# logi-edu.net
KiCad netlist of a schematic drawn in Altium Designer
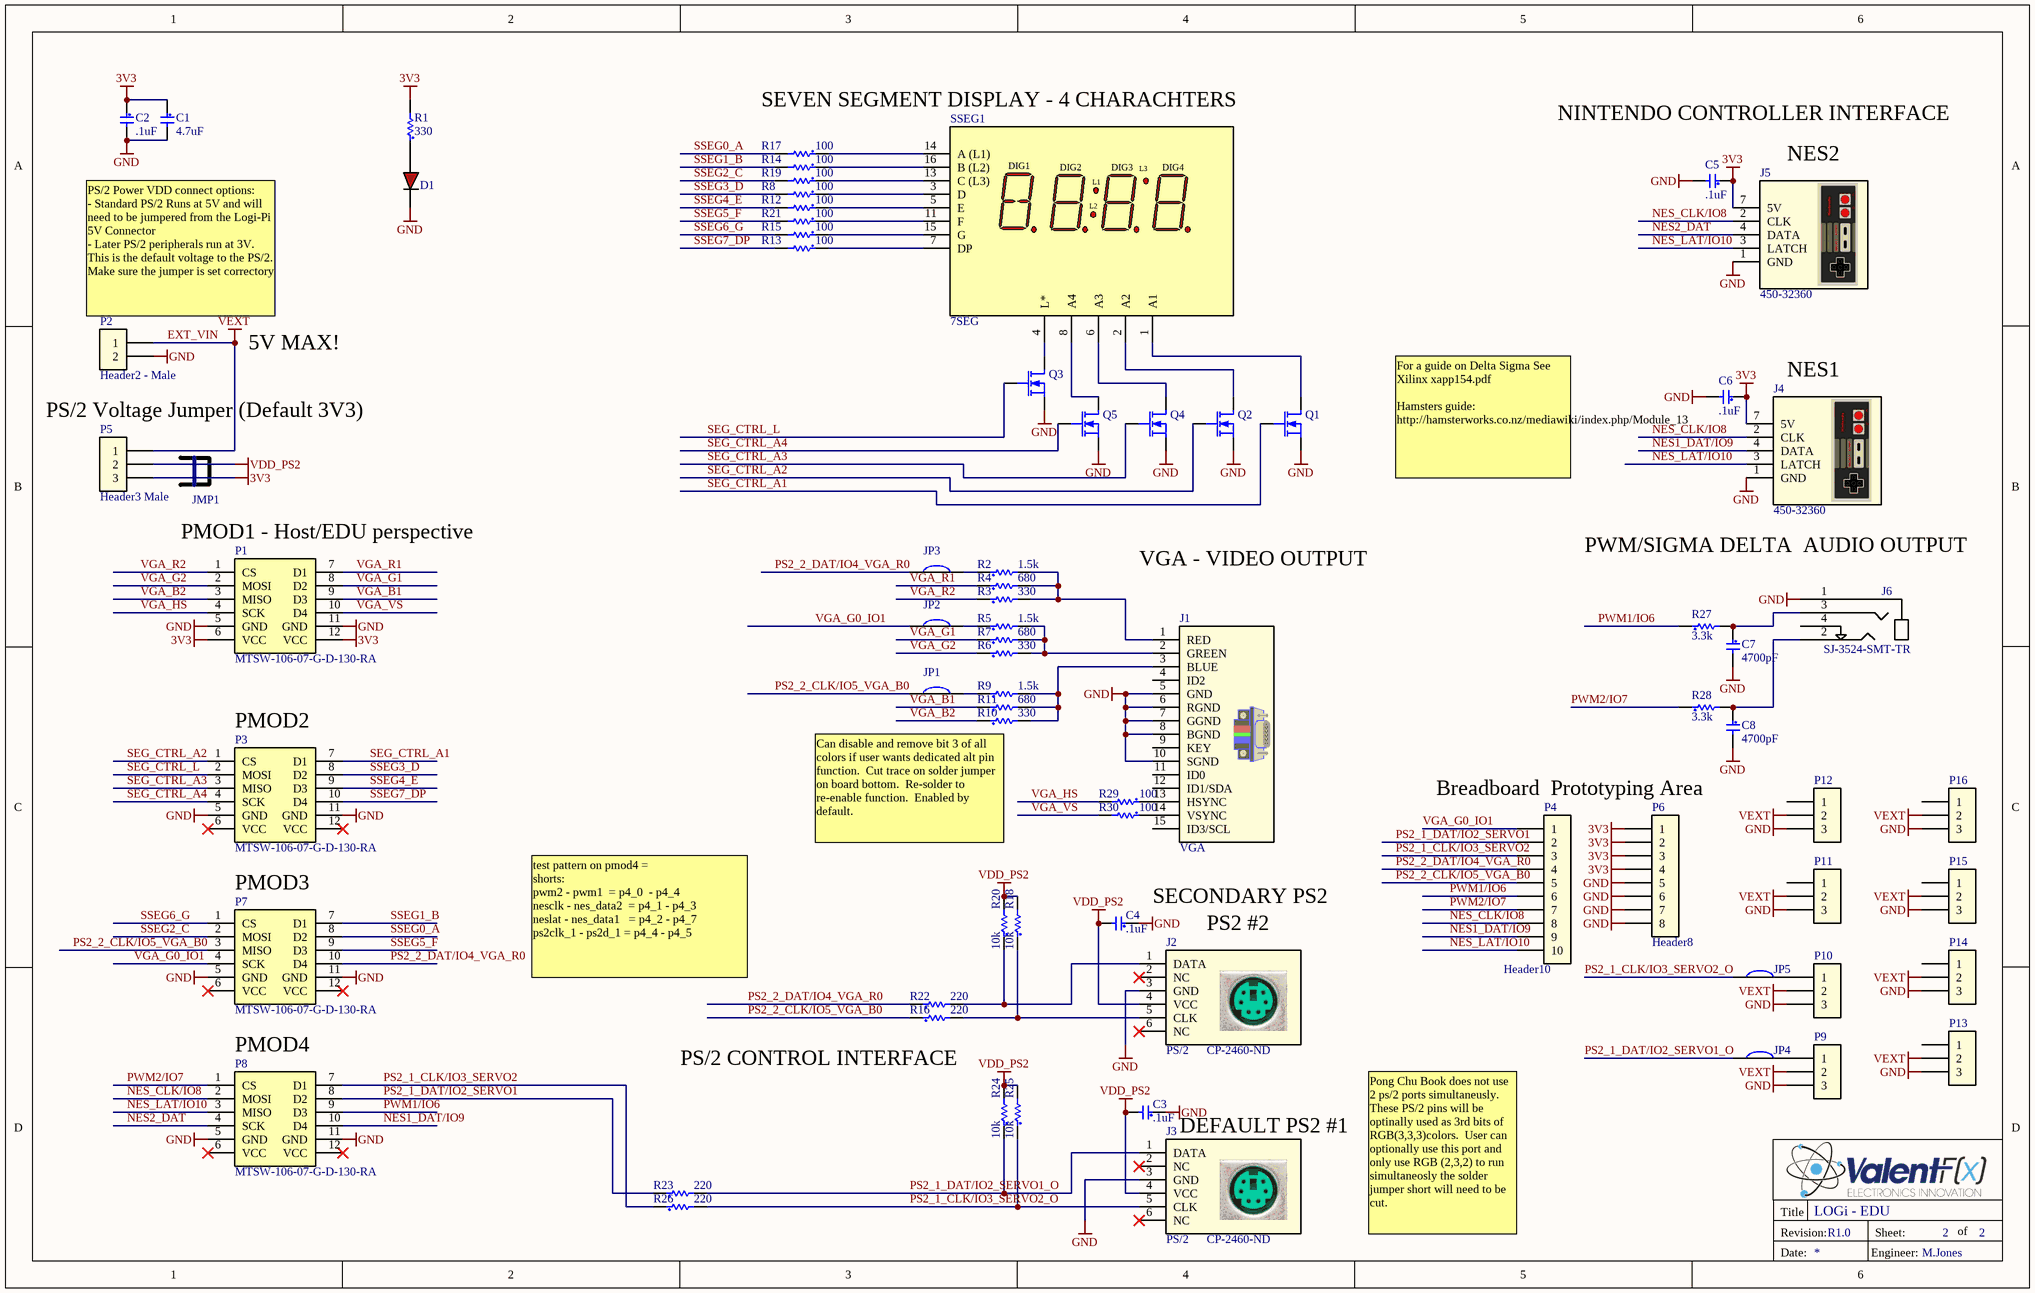
[diagram p0: logi-edu.SchDoc]

(export (version "E")
  (design (tool "Eeschema 10.0.6"))
  (components
    (comp (ref "C1")
      (value "4.7uF")
      (footprint "mRCL:C0603")
      (description "4.7uF 10volts Y5V +80-20% (MLCC) - SMD/SMT 0603")
      (fields
        (field (name "MANUFACTURER") "Murata")
        (field (name "MANUFACTURER PART NUMBER") "GRM188F51A475ZE20D")
      )
      (libsource (lib "mCapacitors") (part "C0603 - GRM188F51A475ZE20D"))
    )
    (comp (ref "C2")
      (value ".1uF")
      (footprint "mRCL:C0603")
      (description "0.1uF 50volts X7R 10% MLCC SMD/SMT 0603")
      (fields
        (field (name "MANUFACTURER") "Murata")
        (field (name "MANUFACTURER PART NUMBER") "GRM188R71H104KA93D")
      )
      (libsource (lib "mCapacitors") (part "C0603 - GRM188R71H104KA93D"))
    )
    (comp (ref "C3")
      (value ".1uF")
      (footprint "mRCL:C0603")
      (description "0.1uF 50volts X7R 10% MLCC SMD/SMT 0603")
      (fields
        (field (name "MANUFACTURER") "Murata")
        (field (name "MANUFACTURER PART NUMBER") "GRM188R71H104KA93D")
      )
      (libsource (lib "mCapacitors") (part "C0603 - GRM188R71H104KA93D"))
    )
    (comp (ref "C4")
      (value ".1uF")
      (footprint "mRCL:C0603")
      (description "0.1uF 50volts X7R 10% MLCC SMD/SMT 0603")
      (fields
        (field (name "MANUFACTURER") "Murata")
        (field (name "MANUFACTURER PART NUMBER") "GRM188R71H104KA93D")
      )
      (libsource (lib "mCapacitors") (part "C0603 - GRM188R71H104KA93D"))
    )
    (comp (ref "C5")
      (value ".1uF")
      (footprint "mRCL:C0603")
      (description "0.1uF 50volts X7R 10% MLCC SMD/SMT 0603")
      (fields
        (field (name "MANUFACTURER") "Murata")
        (field (name "MANUFACTURER PART NUMBER") "GRM188R71H104KA93D")
      )
      (libsource (lib "mCapacitors") (part "C0603 - GRM188R71H104KA93D"))
    )
    (comp (ref "C6")
      (value ".1uF")
      (footprint "mRCL:C0603")
      (description "0.1uF 50volts X7R 10% MLCC SMD/SMT 0603")
      (fields
        (field (name "MANUFACTURER") "Murata")
        (field (name "MANUFACTURER PART NUMBER") "GRM188R71H104KA93D")
      )
      (libsource (lib "mCapacitors") (part "C0603 - GRM188R71H104KA93D"))
    )
    (comp (ref "C7")
      (value "4700pF")
      (footprint "mrcl:C1206")
      (description "CAP CER 4700PF 50V 10% X7R 1206")
      (fields
        (field (name "MANUFACTURER") "Kemet")
        (field (name "MANUFACTURER PART NUMBER") "C1206C472K5RACTU")
      )
      (libsource (lib "mCapacitors") (part "C1206 - C1206C472K5RACTU"))
    )
    (comp (ref "C8")
      (value "4700pF")
      (footprint "mrcl:C1206")
      (description "CAP CER 4700PF 50V 10% X7R 1206")
      (fields
        (field (name "MANUFACTURER") "Kemet")
        (field (name "MANUFACTURER PART NUMBER") "C1206C472K5RACTU")
      )
      (libsource (lib "mCapacitors") (part "C1206 - C1206C472K5RACTU"))
    )
    (comp (ref "D1")
      (value "598-8010-107F")
      (footprint "LED_0603 - RED")
      (description "LED ALINGAP RED CLEAR 0603 SMD")
      (fields (field (name "MANUFACTURER") "Dialight"))
      (libsource (lib "mDiode") (part "LED0603 - 598-8010-107F"))
    )
    (comp (ref "J1")
      (value "VGA")
      (footprint "econnector:1-1734530-1")
      (description "CONN HD D-SUB RCPT R/A 15POS")
      (fields
        (field (name "MANUFACTURER") "TE Connectivity")
        (field (name "MANUFACTURER PART NUMBER") "1-1734530-1")
      )
      (libsource (lib "eConnector") (part "VGA - 1-1734530-1"))
    )
    (comp (ref "J2")
      (value "PS/2")
      (footprint "mconnector:MD-60S - PS/2")
      (description "CONN MINIDIN RECPT UNSHIELD 6POS - PS/2 mouse - keybaord")
      (fields
        (field (name "MANUFACTURER") "CUI Inc")
        (field (name "MANUFACTURER PART NUMBER") "MD-60S")
        (field (name "SUPPLIER PART NUMBER 1") "CP-2460-ND")
      )
      (libsource (lib "mConnector") (part "Con - D-60S"))
    )
    (comp (ref "J3")
      (value "PS/2")
      (footprint "mconnector:MD-60S - PS/2")
      (description "CONN MINIDIN RECPT UNSHIELD 6POS - PS/2 mouse - keybaord")
      (fields
        (field (name "MANUFACTURER") "CUI Inc")
        (field (name "MANUFACTURER PART NUMBER") "MD-60S")
        (field (name "SUPPLIER PART NUMBER 1") "CP-2460-ND")
      )
      (libsource (lib "mConnector") (part "Con - D-60S"))
    )
    (comp (ref "J4")
      (value "450-32360")
      (footprint "NES - 450-32360")
      (description "NES CONTROLLER SOCKET")
      (fields (field (name "MANUFACTURER") "Parallax Inc"))
      (libsource (lib "mConnector") (part "450-32360"))
    )
    (comp (ref "J5")
      (value "450-32360")
      (footprint "NES - 450-32360")
      (description "NES CONTROLLER SOCKET")
      (fields (field (name "MANUFACTURER") "Parallax Inc"))
      (libsource (lib "mConnector") (part "450-32360"))
    )
    (comp (ref "J6")
      (value "SJ-3524-SMT-TR")
      (footprint "SJ-3524-SMT")
      (description "CONN AUDIO JACK 3.5MM STEREO SMD")
      (fields (field (name "MANUFACTURER") "CUI Inc"))
      (libsource (lib "mConnector") (part "SJ-3524-SMT-TR"))
    )
    (comp (ref "JMP1")
      (value "Header Jumper")
      (description "CONN JUMPER SHORTING GOLD FLASH")
      (fields
        (field (name "MANUFACTURER") "Sullins Connector Solutions")
        (field (name "MANUFACTURER PART NUMBER") "SPC02SYAN")
      )
      (libsource (lib "mConnector") (part "JMP - PC02SYAN"))
    )
    (comp (ref "JP1")
      (value "Solder Jumper-NC")
      (footprint "SOLDER_JUMPER-NC")
      (description "Solder/Configuration Jumper")
      (fields (field (name "MANUFACTURER") "n/a"))
      (libsource (lib "mConnector") (part "Solder Jumper-NC"))
    )
    (comp (ref "JP2")
      (value "Solder Jumper-NC")
      (footprint "SOLDER_JUMPER-NC")
      (description "Solder/Configuration Jumper")
      (fields (field (name "MANUFACTURER") "n/a"))
      (libsource (lib "mConnector") (part "Solder Jumper-NC"))
    )
    (comp (ref "JP3")
      (value "Solder Jumper-NC")
      (footprint "SOLDER_JUMPER-NC")
      (description "Solder/Configuration Jumper")
      (fields (field (name "MANUFACTURER") "n/a"))
      (libsource (lib "mConnector") (part "Solder Jumper-NC"))
    )
    (comp (ref "JP4")
      (value "Solder Jumper-NC")
      (footprint "SOLDER_JUMPER-NC")
      (description "Solder/Configuration Jumper")
      (fields (field (name "MANUFACTURER") "n/a"))
      (libsource (lib "mConnector") (part "Solder Jumper-NC"))
    )
    (comp (ref "JP5")
      (value "Solder Jumper-NC")
      (footprint "SOLDER_JUMPER-NC")
      (description "Solder/Configuration Jumper")
      (fields (field (name "MANUFACTURER") "n/a"))
      (libsource (lib "mConnector") (part "Solder Jumper-NC"))
    )
    (comp (ref "P1")
      (value "MTSW-106-07-G-D-130-RA")
      (footprint "mconnector:PMOD HEADER - Male")
      (description "Samtec Male Conn Unshrouded Header HDR 12 POS 2.54mm Solder RA Thru-Hole")
      (fields (field (name "MANUFACTURER") "Samtec"))
      (libsource (lib "mConnector") (part "P-MOD - MTSW-106-07-G-D-130-RA"))
    )
    (comp (ref "P2")
      (value "Header2 - Male")
      (footprint "HDR - PRPC002SAAN-RC")
      (description "2POS male CONN HEADER .100\" SNGL STR")
      (fields
        (field (name "MANUFACTURER") "Sullins Connector Solutions")
        (field (name "MANUFACTURER PART NUMBER") "PRPC002SAAN-RC")
      )
      (libsource (lib "mConnector") (part "HDR - PRPC002SAAN-RC"))
    )
    (comp (ref "P3")
      (value "MTSW-106-07-G-D-130-RA")
      (footprint "mconnector:PMOD HEADER - Male")
      (description "Samtec Male Conn Unshrouded Header HDR 12 POS 2.54mm Solder RA Thru-Hole")
      (fields (field (name "MANUFACTURER") "Samtec"))
      (libsource (lib "mConnector") (part "P-MOD - MTSW-106-07-G-D-130-RA"))
    )
    (comp (ref "P4")
      (value "Header10")
      (footprint "HEADER_10_40_100THRU SIP")
      (description "Header 10 pin")
      (libsource (lib "mConnector") (part "Header10"))
    )
    (comp (ref "P5")
      (value "Header3 Male")
      (footprint "HDR - PRPC003SAAN-RC")
      (description "3POS Male CONN HEADER .100\" SNGL STR")
      (fields
        (field (name "MANUFACTURER") "Sullins Connector Solutions")
        (field (name "MANUFACTURER PART NUMBER") "PRPC003SAAN-RC")
      )
      (libsource (lib "") (part "HDR - PRPC003SAAN-RC_1"))
    )
    (comp (ref "P6")
      (value "Header8")
      (footprint "HEADER_8_40_100THRU SIP")
      (description "Header 8 pin")
      (libsource (lib "mConnector") (part "Header8"))
    )
    (comp (ref "P7")
      (value "MTSW-106-07-G-D-130-RA")
      (footprint "mconnector:PMOD HEADER - Male")
      (description "Samtec Male Conn Unshrouded Header HDR 12 POS 2.54mm Solder RA Thru-Hole")
      (fields (field (name "MANUFACTURER") "Samtec"))
      (libsource (lib "mConnector") (part "P-MOD - MTSW-106-07-G-D-130-RA"))
    )
    (comp (ref "P8")
      (value "MTSW-106-07-G-D-130-RA")
      (footprint "mconnector:PMOD HEADER - Male")
      (description "Samtec Male Conn Unshrouded Header HDR 12 POS 2.54mm Solder RA Thru-Hole")
      (fields (field (name "MANUFACTURER") "Samtec"))
      (libsource (lib "mConnector") (part "P-MOD - MTSW-106-07-G-D-130-RA"))
    )
    (comp (ref "P9")
      (value "Header3 Male")
      (footprint "HDR - PRPC003SAAN-RC")
      (description "3POS Male CONN HEADER .100\" SNGL STR")
      (fields
        (field (name "MANUFACTURER") "Sullins Connector Solutions")
        (field (name "MANUFACTURER PART NUMBER") "PRPC003SAAN-RC")
      )
      (libsource (lib "mConnector") (part "HDR - PRPC003SAAN-RC"))
    )
    (comp (ref "P10")
      (value "Header3 Male")
      (footprint "HDR - PRPC003SAAN-RC")
      (description "3POS Male CONN HEADER .100\" SNGL STR")
      (fields
        (field (name "MANUFACTURER") "Sullins Connector Solutions")
        (field (name "MANUFACTURER PART NUMBER") "PRPC003SAAN-RC")
      )
      (libsource (lib "mConnector") (part "HDR - PRPC003SAAN-RC"))
    )
    (comp (ref "P11")
      (value "Header3 Male")
      (footprint "HDR - PRPC003SAAN-RC")
      (description "3POS Male CONN HEADER .100\" SNGL STR")
      (fields
        (field (name "MANUFACTURER") "Sullins Connector Solutions")
        (field (name "MANUFACTURER PART NUMBER") "PRPC003SAAN-RC")
      )
      (libsource (lib "mConnector") (part "HDR - PRPC003SAAN-RC"))
    )
    (comp (ref "P12")
      (value "Header3 Male")
      (footprint "HDR - PRPC003SAAN-RC")
      (description "3POS Male CONN HEADER .100\" SNGL STR")
      (fields
        (field (name "MANUFACTURER") "Sullins Connector Solutions")
        (field (name "MANUFACTURER PART NUMBER") "PRPC003SAAN-RC")
      )
      (libsource (lib "mConnector") (part "HDR - PRPC003SAAN-RC"))
    )
    (comp (ref "P13")
      (value "Header3 Male")
      (footprint "HDR - PRPC003SAAN-RC")
      (description "3POS Male CONN HEADER .100\" SNGL STR")
      (fields
        (field (name "MANUFACTURER") "Sullins Connector Solutions")
        (field (name "MANUFACTURER PART NUMBER") "PRPC003SAAN-RC")
      )
      (libsource (lib "mConnector") (part "HDR - PRPC003SAAN-RC"))
    )
    (comp (ref "P14")
      (value "Header3 Male")
      (footprint "HDR - PRPC003SAAN-RC")
      (description "3POS Male CONN HEADER .100\" SNGL STR")
      (fields
        (field (name "MANUFACTURER") "Sullins Connector Solutions")
        (field (name "MANUFACTURER PART NUMBER") "PRPC003SAAN-RC")
      )
      (libsource (lib "mConnector") (part "HDR - PRPC003SAAN-RC"))
    )
    (comp (ref "P15")
      (value "Header3 Male")
      (footprint "HDR - PRPC003SAAN-RC")
      (description "3POS Male CONN HEADER .100\" SNGL STR")
      (fields
        (field (name "MANUFACTURER") "Sullins Connector Solutions")
        (field (name "MANUFACTURER PART NUMBER") "PRPC003SAAN-RC")
      )
      (libsource (lib "mConnector") (part "HDR - PRPC003SAAN-RC"))
    )
    (comp (ref "P16")
      (value "Header3 Male")
      (footprint "HDR - PRPC003SAAN-RC")
      (description "3POS Male CONN HEADER .100\" SNGL STR")
      (fields
        (field (name "MANUFACTURER") "Sullins Connector Solutions")
        (field (name "MANUFACTURER PART NUMBER") "PRPC003SAAN-RC")
      )
      (libsource (lib "mConnector") (part "HDR - PRPC003SAAN-RC"))
    )
    (comp (ref "Q1")
      (value "DMN65D8L-7")
      (footprint "sot-23")
      (description "MOSFET N-CH 60V 310MA SOT23")
      (fields (field (name "MANUFACTURER") "Diodes Incorporated"))
      (libsource (lib "mTransistor") (part "NMOS - DMN65D8L-7"))
    )
    (comp (ref "Q2")
      (value "DMN65D8L-7")
      (footprint "sot-23")
      (description "MOSFET N-CH 60V 310MA SOT23")
      (fields (field (name "MANUFACTURER") "Diodes Incorporated"))
      (libsource (lib "mTransistor") (part "NMOS - DMN65D8L-7"))
    )
    (comp (ref "Q3")
      (value "DMN65D8L-7")
      (footprint "sot-23")
      (description "MOSFET N-CH 60V 310MA SOT23")
      (fields (field (name "MANUFACTURER") "Diodes Incorporated"))
      (libsource (lib "mTransistor") (part "NMOS - DMN65D8L-7"))
    )
    (comp (ref "Q4")
      (value "DMN65D8L-7")
      (footprint "sot-23")
      (description "MOSFET N-CH 60V 310MA SOT23")
      (fields (field (name "MANUFACTURER") "Diodes Incorporated"))
      (libsource (lib "mTransistor") (part "NMOS - DMN65D8L-7"))
    )
    (comp (ref "Q5")
      (value "DMN65D8L-7")
      (footprint "sot-23")
      (description "MOSFET N-CH 60V 310MA SOT23")
      (fields (field (name "MANUFACTURER") "Diodes Incorporated"))
      (libsource (lib "mTransistor") (part "NMOS - DMN65D8L-7"))
    )
    (comp (ref "R1")
      (value "330")
      (footprint "mRCL:R0603")
      (description "RES 330 OHM 1/10W 1% 0603 SMD")
      (fields
        (field (name "MANUFACTURER") "Panasonic Electronic Components")
        (field (name "MANUFACTURER PART NUMBER") "ERJ-3EKF3300V")
      )
      (libsource (lib "mResistors") (part "R0603 - ERJ-3EKF3300V"))
    )
    (comp (ref "R2")
      (value "1.5k")
      (footprint "mRCL:R0603")
      (description "RES 1.5K OHM 1/10W 1% 0603 SMD")
      (fields
        (field (name "MANUFACTURER") "Panasonic Electronic Components")
        (field (name "MANUFACTURER PART NUMBER") "ERJ-3EKF1501V")
      )
      (libsource (lib "mResistors") (part "R0603 - ERJ-3EKF1501V"))
    )
    (comp (ref "R3")
      (value "330")
      (footprint "mRCL:R0603")
      (description "RES 330 OHM 1/10W 1% 0603 SMD")
      (fields
        (field (name "MANUFACTURER") "Panasonic Electronic Components")
        (field (name "MANUFACTURER PART NUMBER") "ERJ-3EKF3300V")
      )
      (libsource (lib "mResistors") (part "R0603 - ERJ-3EKF3300V"))
    )
    (comp (ref "R4")
      (value "680")
      (footprint "mRCL:R0603")
      (description "RES 680 OHM 1/10W 1% 0603 SMD")
      (fields
        (field (name "MANUFACTURER") "Panasonic Electronic Components")
        (field (name "MANUFACTURER PART NUMBER") "ERJ-3EKF6800V")
      )
      (libsource (lib "mResistors") (part "R0603 - ERJ-3EKF6800V"))
    )
    (comp (ref "R5")
      (value "1.5k")
      (footprint "mRCL:R0603")
      (description "RES 1.5K OHM 1/10W 1% 0603 SMD")
      (fields
        (field (name "MANUFACTURER") "Panasonic Electronic Components")
        (field (name "MANUFACTURER PART NUMBER") "ERJ-3EKF1501V")
      )
      (libsource (lib "mResistors") (part "R0603 - ERJ-3EKF1501V"))
    )
    (comp (ref "R6")
      (value "330")
      (footprint "mRCL:R0603")
      (description "RES 330 OHM 1/10W 1% 0603 SMD")
      (fields
        (field (name "MANUFACTURER") "Panasonic Electronic Components")
        (field (name "MANUFACTURER PART NUMBER") "ERJ-3EKF3300V")
      )
      (libsource (lib "mResistors") (part "R0603 - ERJ-3EKF3300V"))
    )
    (comp (ref "R7")
      (value "680")
      (footprint "mRCL:R0603")
      (description "RES 680 OHM 1/10W 1% 0603 SMD")
      (fields
        (field (name "MANUFACTURER") "Panasonic Electronic Components")
        (field (name "MANUFACTURER PART NUMBER") "ERJ-3EKF6800V")
      )
      (libsource (lib "mResistors") (part "R0603 - ERJ-3EKF6800V"))
    )
    (comp (ref "R8")
      (value "100")
      (footprint "mRCL:R0603")
      (description "100 ohms 1% Thick Film Resistors - SMD 1/10watt")
      (fields
        (field (name "MANUFACTURER") "Vishay/Dale")
        (field (name "MANUFACTURER PART NUMBER") "CRCW0603100RFKEA")
      )
      (libsource (lib "mResistors") (part "R0603 - CRCW0603100RFKEA"))
    )
    (comp (ref "R9")
      (value "1.5k")
      (footprint "mRCL:R0603")
      (description "RES 1.5K OHM 1/10W 1% 0603 SMD")
      (fields
        (field (name "MANUFACTURER") "Panasonic Electronic Components")
        (field (name "MANUFACTURER PART NUMBER") "ERJ-3EKF1501V")
      )
      (libsource (lib "mResistors") (part "R0603 - ERJ-3EKF1501V"))
    )
    (comp (ref "R10")
      (value "330")
      (footprint "mRCL:R0603")
      (description "RES 330 OHM 1/10W 1% 0603 SMD")
      (fields
        (field (name "MANUFACTURER") "Panasonic Electronic Components")
        (field (name "MANUFACTURER PART NUMBER") "ERJ-3EKF3300V")
      )
      (libsource (lib "mResistors") (part "R0603 - ERJ-3EKF3300V"))
    )
    (comp (ref "R11")
      (value "680")
      (footprint "mRCL:R0603")
      (description "RES 680 OHM 1/10W 1% 0603 SMD")
      (fields
        (field (name "MANUFACTURER") "Panasonic Electronic Components")
        (field (name "MANUFACTURER PART NUMBER") "ERJ-3EKF6800V")
      )
      (libsource (lib "mResistors") (part "R0603 - ERJ-3EKF6800V"))
    )
    (comp (ref "R12")
      (value "100")
      (footprint "mRCL:R0603")
      (description "100 ohms 1% Thick Film Resistors - SMD 1/10watt")
      (fields
        (field (name "MANUFACTURER") "Vishay/Dale")
        (field (name "MANUFACTURER PART NUMBER") "CRCW0603100RFKEA")
      )
      (libsource (lib "mResistors") (part "R0603 - CRCW0603100RFKEA"))
    )
    (comp (ref "R13")
      (value "100")
      (footprint "mRCL:R0603")
      (description "100 ohms 1% Thick Film Resistors - SMD 1/10watt")
      (fields
        (field (name "MANUFACTURER") "Vishay/Dale")
        (field (name "MANUFACTURER PART NUMBER") "CRCW0603100RFKEA")
      )
      (libsource (lib "mResistors") (part "R0603 - CRCW0603100RFKEA"))
    )
    (comp (ref "R14")
      (value "100")
      (footprint "mRCL:R0603")
      (description "100 ohms 1% Thick Film Resistors - SMD 1/10watt")
      (fields
        (field (name "MANUFACTURER") "Vishay/Dale")
        (field (name "MANUFACTURER PART NUMBER") "CRCW0603100RFKEA")
      )
      (libsource (lib "mResistors") (part "R0603 - CRCW0603100RFKEA"))
    )
    (comp (ref "R15")
      (value "100")
      (footprint "mRCL:R0603")
      (description "100 ohms 1% Thick Film Resistors - SMD 1/10watt")
      (fields
        (field (name "MANUFACTURER") "Vishay/Dale")
        (field (name "MANUFACTURER PART NUMBER") "CRCW0603100RFKEA")
      )
      (libsource (lib "mResistors") (part "R0603 - CRCW0603100RFKEA"))
    )
    (comp (ref "R16")
      (value "220")
      (footprint "mRCL:R0603")
      (description "220 - thick Film Resistors - SMD 0603 220ohms 1% Tol")
      (fields
        (field (name "MANUFACTURER") "Panasonic - ECG")
        (field (name "MANUFACTURER PART NUMBER") "ERJ-3EKF2200V")
      )
      (libsource (lib "mResistors") (part "R0603 - ERJ-3EKF2200V"))
    )
    (comp (ref "R17")
      (value "100")
      (footprint "mRCL:R0603")
      (description "100 ohms 1% Thick Film Resistors - SMD 1/10watt")
      (fields
        (field (name "MANUFACTURER") "Vishay/Dale")
        (field (name "MANUFACTURER PART NUMBER") "CRCW0603100RFKEA")
      )
      (libsource (lib "mResistors") (part "R0603 - CRCW0603100RFKEA"))
    )
    (comp (ref "R18")
      (value "10k")
      (footprint "mRCL:R0603")
      (description "10k Thick Film Resistors - SMD 1/10watt 10Kohms 1%")
      (fields
        (field (name "MANUFACTURER") "Vishay Dale")
        (field (name "MANUFACTURER PART NUMBER") "CRCW060310K0FKEA")
      )
      (libsource (lib "mResistors") (part "R0603 - CRCW060310K0FKEA"))
    )
    (comp (ref "R19")
      (value "100")
      (footprint "mRCL:R0603")
      (description "100 ohms 1% Thick Film Resistors - SMD 1/10watt")
      (fields
        (field (name "MANUFACTURER") "Vishay/Dale")
        (field (name "MANUFACTURER PART NUMBER") "CRCW0603100RFKEA")
      )
      (libsource (lib "mResistors") (part "R0603 - CRCW0603100RFKEA"))
    )
    (comp (ref "R20")
      (value "10k")
      (footprint "mRCL:R0603")
      (description "10k Thick Film Resistors - SMD 1/10watt 10Kohms 1%")
      (fields
        (field (name "MANUFACTURER") "Vishay Dale")
        (field (name "MANUFACTURER PART NUMBER") "CRCW060310K0FKEA")
      )
      (libsource (lib "mResistors") (part "R0603 - CRCW060310K0FKEA"))
    )
    (comp (ref "R21")
      (value "100")
      (footprint "mRCL:R0603")
      (description "100 ohms 1% Thick Film Resistors - SMD 1/10watt")
      (fields
        (field (name "MANUFACTURER") "Vishay/Dale")
        (field (name "MANUFACTURER PART NUMBER") "CRCW0603100RFKEA")
      )
      (libsource (lib "mResistors") (part "R0603 - CRCW0603100RFKEA"))
    )
    (comp (ref "R22")
      (value "220")
      (footprint "mRCL:R0603")
      (description "220 - thick Film Resistors - SMD 0603 220ohms 1% Tol")
      (fields
        (field (name "MANUFACTURER") "Panasonic - ECG")
        (field (name "MANUFACTURER PART NUMBER") "ERJ-3EKF2200V")
      )
      (libsource (lib "mResistors") (part "R0603 - ERJ-3EKF2200V"))
    )
    (comp (ref "R23")
      (value "220")
      (footprint "mRCL:R0603")
      (description "220 - thick Film Resistors - SMD 0603 220ohms 1% Tol")
      (fields
        (field (name "MANUFACTURER") "Panasonic - ECG")
        (field (name "MANUFACTURER PART NUMBER") "ERJ-3EKF2200V")
      )
      (libsource (lib "mResistors") (part "R0603 - ERJ-3EKF2200V"))
    )
    (comp (ref "R24")
      (value "10k")
      (footprint "mRCL:R0603")
      (description "10k Thick Film Resistors - SMD 1/10watt 10Kohms 1%")
      (fields
        (field (name "MANUFACTURER") "Vishay Dale")
        (field (name "MANUFACTURER PART NUMBER") "CRCW060310K0FKEA")
      )
      (libsource (lib "mResistors") (part "R0603 - CRCW060310K0FKEA"))
    )
    (comp (ref "R25")
      (value "10k")
      (footprint "mRCL:R0603")
      (description "10k Thick Film Resistors - SMD 1/10watt 10Kohms 1%")
      (fields
        (field (name "MANUFACTURER") "Vishay Dale")
        (field (name "MANUFACTURER PART NUMBER") "CRCW060310K0FKEA")
      )
      (libsource (lib "mResistors") (part "R0603 - CRCW060310K0FKEA"))
    )
    (comp (ref "R26")
      (value "220")
      (footprint "mRCL:R0603")
      (description "220 - thick Film Resistors - SMD 0603 220ohms 1% Tol")
      (fields
        (field (name "MANUFACTURER") "Panasonic - ECG")
        (field (name "MANUFACTURER PART NUMBER") "ERJ-3EKF2200V")
      )
      (libsource (lib "mResistors") (part "R0603 - ERJ-3EKF2200V"))
    )
    (comp (ref "R27")
      (value "3.3k")
      (footprint "R1206")
      (description "RES 3.3K OHM 1/4W 1% 1206 SMD")
      (fields
        (field (name "MANUFACTURER") "Panasonic Electronic Components")
        (field (name "MANUFACTURER PART NUMBER") "ERJ-8ENF3301V")
      )
      (libsource (lib "mResistors") (part "R1206 - ERJ-8ENF3301V"))
    )
    (comp (ref "R28")
      (value "3.3k")
      (footprint "R1206")
      (description "RES 3.3K OHM 1/4W 1% 1206 SMD")
      (fields
        (field (name "MANUFACTURER") "Panasonic Electronic Components")
        (field (name "MANUFACTURER PART NUMBER") "ERJ-8ENF3301V")
      )
      (libsource (lib "mResistors") (part "R1206 - ERJ-8ENF3301V"))
    )
    (comp (ref "R29")
      (value "100")
      (footprint "mRCL:R0603")
      (description "100 ohms 1% Thick Film Resistors - SMD 1/10watt")
      (fields
        (field (name "MANUFACTURER") "Vishay/Dale")
        (field (name "MANUFACTURER PART NUMBER") "CRCW0603100RFKEA")
      )
      (libsource (lib "mResistors") (part "R0603 - CRCW0603100RFKEA"))
    )
    (comp (ref "R30")
      (value "100")
      (footprint "mRCL:R0603")
      (description "100 ohms 1% Thick Film Resistors - SMD 1/10watt")
      (fields
        (field (name "MANUFACTURER") "Vishay/Dale")
        (field (name "MANUFACTURER PART NUMBER") "CRCW0603100RFKEA")
      )
      (libsource (lib "mResistors") (part "R0603 - CRCW0603100RFKEA"))
    )
    (comp (ref "SSEG1")
      (value "7SEG")
      (footprint "LED - SSEG - LTC-4727JR")
      (description "LED Displays & Accessories 4 Digit, Red Low Current")
      (fields (field (name "MANUFACTURER") "Lite-On") (field (name "MANUFACTURER PART NUMBER") "LTC-4727JR"))
      (libsource (lib "eDiode") (part "LED - SSEG - LTC-4727JR"))
    )
  )
  (nets
    (net (code "1") (name "/NES1_DAT{slash}IO9") (class "Default")
      (node (ref "J4") (pin "4") (pinfunction "DATA_4") (pintype "passive"))
      (node (ref "P4") (pin "9") (pinfunction "9_9") (pintype "passive"))
      (node (ref "P8") (pin "10") (pinfunction "D4_10") (pintype "power_in"))
    )
    (net (code "2") (name "/NES2_DAT") (class "Default")
      (node (ref "J5") (pin "4") (pinfunction "DATA_4") (pintype "passive"))
      (node (ref "P8") (pin "4") (pinfunction "SCK_4") (pintype "power_in"))
    )
    (net (code "3") (name "/NES_CLK{slash}IO8") (class "Default")
      (node (ref "J4") (pin "2") (pinfunction "CLK_2") (pintype "passive"))
      (node (ref "J5") (pin "2") (pinfunction "CLK_2") (pintype "passive"))
      (node (ref "P4") (pin "8") (pinfunction "8_8") (pintype "passive"))
      (node (ref "P8") (pin "2") (pinfunction "MOSI_2") (pintype "power_in"))
    )
    (net (code "4") (name "/NES_LAT{slash}IO10") (class "Default")
      (node (ref "J4") (pin "3") (pinfunction "LATCH_3") (pintype "passive"))
      (node (ref "J5") (pin "3") (pinfunction "LATCH_3") (pintype "passive"))
      (node (ref "P4") (pin "10") (pinfunction "10_10") (pintype "passive"))
      (node (ref "P8") (pin "3") (pinfunction "MISO_3") (pintype "power_in"))
    )
    (net (code "5") (name "/PS2_1_CLK{slash}IO3_SERVO2") (class "Default")
      (node (ref "P4") (pin "3") (pinfunction "3_3") (pintype "passive"))
      (node (ref "P8") (pin "7") (pinfunction "D1_7") (pintype "power_in"))
      (node (ref "R26") (pin "1") (pinfunction "1_1") (pintype "passive"))
    )
    (net (code "6") (name "/PS2_1_CLK{slash}IO3_SERVO2_O") (class "Default")
      (node (ref "J3") (pin "5") (pinfunction "CLK_5") (pintype "passive"))
      (node (ref "JP5") (pin "1") (pinfunction "1_1") (pintype "passive"))
      (node (ref "R25") (pin "1") (pinfunction "1_1") (pintype "passive"))
      (node (ref "R26") (pin "2") (pinfunction "2_2") (pintype "passive"))
    )
    (net (code "7") (name "/PS2_1_DAT{slash}IO2_SERVO1") (class "Default")
      (node (ref "P4") (pin "2") (pinfunction "2_2") (pintype "passive"))
      (node (ref "P8") (pin "8") (pinfunction "D2_8") (pintype "power_in"))
      (node (ref "R23") (pin "1") (pinfunction "1_1") (pintype "passive"))
    )
    (net (code "8") (name "/PS2_1_DAT{slash}IO2_SERVO1_O") (class "Default")
      (node (ref "J3") (pin "1") (pinfunction "DATA_1") (pintype "passive"))
      (node (ref "JP4") (pin "1") (pinfunction "1_1") (pintype "passive"))
      (node (ref "R23") (pin "2") (pinfunction "2_2") (pintype "passive"))
      (node (ref "R24") (pin "1") (pinfunction "1_1") (pintype "passive"))
    )
    (net (code "9") (name "/PS2_2_CLK{slash}IO5_VGA_B0") (class "Default")
      (node (ref "JP1") (pin "1") (pinfunction "1_1") (pintype "passive"))
      (node (ref "P4") (pin "5") (pinfunction "5_5") (pintype "passive"))
      (node (ref "P7") (pin "3") (pinfunction "MISO_3") (pintype "power_in"))
      (node (ref "R16") (pin "1") (pinfunction "1_1") (pintype "passive"))
    )
    (net (code "10") (name "/PS2_2_DAT{slash}IO4_VGA_R0") (class "Default")
      (node (ref "JP3") (pin "1") (pinfunction "1_1") (pintype "passive"))
      (node (ref "P4") (pin "4") (pinfunction "4_4") (pintype "passive"))
      (node (ref "P7") (pin "10") (pinfunction "D4_10") (pintype "power_in"))
      (node (ref "R22") (pin "1") (pinfunction "1_1") (pintype "passive"))
    )
    (net (code "11") (name "/PWM1{slash}IO6") (class "Default")
      (node (ref "P4") (pin "6") (pinfunction "6_6") (pintype "passive"))
      (node (ref "P8") (pin "9") (pinfunction "D3_9") (pintype "power_in"))
      (node (ref "R27") (pin "1") (pinfunction "1_1") (pintype "passive"))
    )
    (net (code "12") (name "/PWM2{slash}IO7") (class "Default")
      (node (ref "P4") (pin "7") (pinfunction "7_7") (pintype "passive"))
      (node (ref "P8") (pin "1") (pinfunction "CS_1") (pintype "power_in"))
      (node (ref "R28") (pin "1") (pinfunction "1_1") (pintype "passive"))
    )
    (net (code "13") (name "/SEG_CTRL_A1") (class "Default")
      (node (ref "P3") (pin "7") (pinfunction "D1_7") (pintype "power_in"))
      (node (ref "Q1") (pin "1") (pinfunction "G_1") (pintype "passive"))
    )
    (net (code "14") (name "/SEG_CTRL_A2") (class "Default")
      (node (ref "P3") (pin "1") (pinfunction "CS_1") (pintype "power_in"))
      (node (ref "Q2") (pin "1") (pinfunction "G_1") (pintype "passive"))
    )
    (net (code "15") (name "/SEG_CTRL_A3") (class "Default")
      (node (ref "P3") (pin "3") (pinfunction "MISO_3") (pintype "power_in"))
      (node (ref "Q4") (pin "1") (pinfunction "G_1") (pintype "passive"))
    )
    (net (code "16") (name "/SEG_CTRL_A4") (class "Default")
      (node (ref "P3") (pin "4") (pinfunction "SCK_4") (pintype "power_in"))
      (node (ref "Q5") (pin "1") (pinfunction "G_1") (pintype "passive"))
    )
    (net (code "17") (name "/SEG_CTRL_L") (class "Default")
      (node (ref "P3") (pin "2") (pinfunction "MOSI_2") (pintype "power_in"))
      (node (ref "Q3") (pin "1") (pinfunction "G_1") (pintype "passive"))
    )
    (net (code "18") (name "/SSEG0_A") (class "Default")
      (node (ref "P7") (pin "8") (pinfunction "D2_8") (pintype "power_in"))
      (node (ref "R17") (pin "2") (pinfunction "2_2") (pintype "passive"))
    )
    (net (code "19") (name "/SSEG1_B") (class "Default")
      (node (ref "P7") (pin "7") (pinfunction "D1_7") (pintype "power_in"))
      (node (ref "R14") (pin "2") (pinfunction "2_2") (pintype "passive"))
    )
    (net (code "20") (name "/SSEG2_C") (class "Default")
      (node (ref "P7") (pin "2") (pinfunction "MOSI_2") (pintype "power_in"))
      (node (ref "R19") (pin "2") (pinfunction "2_2") (pintype "passive"))
    )
    (net (code "21") (name "/SSEG3_D") (class "Default")
      (node (ref "P3") (pin "8") (pinfunction "D2_8") (pintype "power_in"))
      (node (ref "R8") (pin "2") (pinfunction "2_2") (pintype "passive"))
    )
    (net (code "22") (name "/SSEG4_E") (class "Default")
      (node (ref "P3") (pin "9") (pinfunction "D3_9") (pintype "power_in"))
      (node (ref "R12") (pin "2") (pinfunction "2_2") (pintype "passive"))
    )
    (net (code "23") (name "/SSEG5_F") (class "Default")
      (node (ref "P7") (pin "9") (pinfunction "D3_9") (pintype "power_in"))
      (node (ref "R21") (pin "2") (pinfunction "2_2") (pintype "passive"))
    )
    (net (code "24") (name "/SSEG6_G") (class "Default")
      (node (ref "P7") (pin "1") (pinfunction "CS_1") (pintype "power_in"))
      (node (ref "R15") (pin "2") (pinfunction "2_2") (pintype "passive"))
    )
    (net (code "25") (name "/SSEG7_DP") (class "Default")
      (node (ref "P3") (pin "10") (pinfunction "D4_10") (pintype "power_in"))
      (node (ref "R13") (pin "2") (pinfunction "2_2") (pintype "passive"))
    )
    (net (code "26") (name "/VGA_B1") (class "Default")
      (node (ref "P1") (pin "9") (pinfunction "D3_9") (pintype "power_in"))
      (node (ref "R11") (pin "1") (pinfunction "1_1") (pintype "passive"))
    )
    (net (code "27") (name "/VGA_B2") (class "Default")
      (node (ref "P1") (pin "3") (pinfunction "MISO_3") (pintype "power_in"))
      (node (ref "R10") (pin "1") (pinfunction "1_1") (pintype "passive"))
    )
    (net (code "28") (name "/VGA_G0_IO1") (class "Default")
      (node (ref "JP2") (pin "1") (pinfunction "1_1") (pintype "passive"))
      (node (ref "P4") (pin "1") (pinfunction "1_1") (pintype "passive"))
      (node (ref "P7") (pin "4") (pinfunction "SCK_4") (pintype "power_in"))
    )
    (net (code "29") (name "/VGA_G1") (class "Default")
      (node (ref "P1") (pin "8") (pinfunction "D2_8") (pintype "power_in"))
      (node (ref "R7") (pin "1") (pinfunction "1_1") (pintype "passive"))
    )
    (net (code "30") (name "/VGA_G2") (class "Default")
      (node (ref "P1") (pin "2") (pinfunction "MOSI_2") (pintype "power_in"))
      (node (ref "R6") (pin "1") (pinfunction "1_1") (pintype "passive"))
    )
    (net (code "31") (name "/VGA_HS") (class "Default")
      (node (ref "P1") (pin "4") (pinfunction "SCK_4") (pintype "power_in"))
      (node (ref "R29") (pin "2") (pinfunction "2_2") (pintype "passive"))
    )
    (net (code "32") (name "/VGA_R1") (class "Default")
      (node (ref "P1") (pin "7") (pinfunction "D1_7") (pintype "power_in"))
      (node (ref "R4") (pin "1") (pinfunction "1_1") (pintype "passive"))
    )
    (net (code "33") (name "/VGA_R2") (class "Default")
      (node (ref "P1") (pin "1") (pinfunction "CS_1") (pintype "power_in"))
      (node (ref "R3") (pin "1") (pinfunction "1_1") (pintype "passive"))
    )
    (net (code "34") (name "/VGA_VS") (class "Default")
      (node (ref "P1") (pin "10") (pinfunction "D4_10") (pintype "power_in"))
      (node (ref "R30") (pin "2") (pinfunction "2_2") (pintype "passive"))
    )
    (net (code "35") (name "3V3") (class "Default")
      (node (ref "C1") (pin "1") (pinfunction "1_1") (pintype "passive"))
      (node (ref "C2") (pin "1") (pinfunction "1_1") (pintype "passive"))
      (node (ref "C5") (pin "1") (pinfunction "1_1") (pintype "passive"))
      (node (ref "C6") (pin "1") (pinfunction "1_1") (pintype "passive"))
      (node (ref "J4") (pin "7") (pinfunction "5V_7") (pintype "passive"))
      (node (ref "J5") (pin "7") (pinfunction "5V_7") (pintype "passive"))
      (node (ref "P1") (pin "12") (pinfunction "VCC_12") (pintype "power_in"))
      (node (ref "P1") (pin "6") (pinfunction "VCC_6") (pintype "power_in"))
      (node (ref "P5") (pin "3") (pinfunction "3_3") (pintype "passive"))
      (node (ref "P6") (pin "1") (pinfunction "1_1") (pintype "passive"))
      (node (ref "P6") (pin "2") (pinfunction "2_2") (pintype "passive"))
      (node (ref "P6") (pin "3") (pinfunction "3_3") (pintype "passive"))
      (node (ref "P6") (pin "4") (pinfunction "4_4") (pintype "passive"))
      (node (ref "R1") (pin "2") (pinfunction "2_2") (pintype "passive"))
    )
    (net (code "36") (name "GND") (class "Default")
      (node (ref "C1") (pin "2") (pinfunction "2_2") (pintype "passive"))
      (node (ref "C2") (pin "2") (pinfunction "2_2") (pintype "passive"))
      (node (ref "C3") (pin "1") (pinfunction "1_1") (pintype "passive"))
      (node (ref "C4") (pin "1") (pinfunction "1_1") (pintype "passive"))
      (node (ref "C5") (pin "2") (pinfunction "2_2") (pintype "passive"))
      (node (ref "C6") (pin "2") (pinfunction "2_2") (pintype "passive"))
      (node (ref "C7") (pin "2") (pinfunction "2_2") (pintype "passive"))
      (node (ref "C8") (pin "2") (pinfunction "2_2") (pintype "passive"))
      (node (ref "D1") (pin "C") (pinfunction "C_C") (pintype "passive"))
      (node (ref "J1") (pin "10") (pinfunction "SGND_10") (pintype "passive"))
      (node (ref "J1") (pin "5") (pinfunction "GND_5") (pintype "passive"))
      (node (ref "J1") (pin "6") (pinfunction "RGND_6") (pintype "passive"))
      (node (ref "J1") (pin "7") (pinfunction "GGND_7") (pintype "passive"))
      (node (ref "J1") (pin "8") (pinfunction "BGND_8") (pintype "passive"))
      (node (ref "J2") (pin "3") (pinfunction "GND_3") (pintype "passive"))
      (node (ref "J3") (pin "3") (pinfunction "GND_3") (pintype "passive"))
      (node (ref "J4") (pin "1") (pinfunction "GND_1") (pintype "passive"))
      (node (ref "J5") (pin "1") (pinfunction "GND_1") (pintype "passive"))
      (node (ref "J6") (pin "1") (pinfunction "1_1") (pintype "passive"))
      (node (ref "P1") (pin "11") (pinfunction "GND_11") (pintype "power_in"))
      (node (ref "P1") (pin "5") (pinfunction "GND_5") (pintype "power_in"))
      (node (ref "P10") (pin "3") (pinfunction "3_3") (pintype "passive"))
      (node (ref "P11") (pin "3") (pinfunction "3_3") (pintype "passive"))
      (node (ref "P12") (pin "3") (pinfunction "3_3") (pintype "passive"))
      (node (ref "P13") (pin "3") (pinfunction "3_3") (pintype "passive"))
      (node (ref "P14") (pin "3") (pinfunction "3_3") (pintype "passive"))
      (node (ref "P15") (pin "3") (pinfunction "3_3") (pintype "passive"))
      (node (ref "P16") (pin "3") (pinfunction "3_3") (pintype "passive"))
      (node (ref "P2") (pin "2") (pinfunction "2_2") (pintype "passive"))
      (node (ref "P3") (pin "11") (pinfunction "GND_11") (pintype "power_in"))
      (node (ref "P3") (pin "5") (pinfunction "GND_5") (pintype "power_in"))
      (node (ref "P6") (pin "5") (pinfunction "5_5") (pintype "passive"))
      (node (ref "P6") (pin "6") (pinfunction "6_6") (pintype "passive"))
      (node (ref "P6") (pin "7") (pinfunction "7_7") (pintype "passive"))
      (node (ref "P6") (pin "8") (pinfunction "8_8") (pintype "passive"))
      (node (ref "P7") (pin "11") (pinfunction "GND_11") (pintype "power_in"))
      (node (ref "P7") (pin "5") (pinfunction "GND_5") (pintype "power_in"))
      (node (ref "P8") (pin "11") (pinfunction "GND_11") (pintype "power_in"))
      (node (ref "P8") (pin "5") (pinfunction "GND_5") (pintype "power_in"))
      (node (ref "P9") (pin "3") (pinfunction "3_3") (pintype "passive"))
      (node (ref "Q1") (pin "2") (pinfunction "2_2") (pintype "passive"))
      (node (ref "Q2") (pin "2") (pinfunction "2_2") (pintype "passive"))
      (node (ref "Q3") (pin "2") (pinfunction "2_2") (pintype "passive"))
      (node (ref "Q4") (pin "2") (pinfunction "2_2") (pintype "passive"))
      (node (ref "Q5") (pin "2") (pinfunction "2_2") (pintype "passive"))
    )
    (net (code "37") (name "Net-(C7-Pad1)") (class "Default")
      (node (ref "C7") (pin "1") (pinfunction "1_1") (pintype "passive"))
      (node (ref "J6") (pin "3") (pinfunction "3_3") (pintype "passive"))
      (node (ref "R27") (pin "2") (pinfunction "2_2") (pintype "passive"))
    )
    (net (code "38") (name "Net-(C8-Pad1)") (class "Default")
      (node (ref "C8") (pin "1") (pinfunction "1_1") (pintype "passive"))
      (node (ref "J6") (pin "2") (pinfunction "2_2") (pintype "passive"))
      (node (ref "R28") (pin "2") (pinfunction "2_2") (pintype "passive"))
    )
    (net (code "39") (name "Net-(D1-PadA)") (class "Default")
      (node (ref "D1") (pin "A") (pinfunction "A_A") (pintype "passive"))
      (node (ref "R1") (pin "1") (pinfunction "1_1") (pintype "passive"))
    )
    (net (code "40") (name "Net-(J1-BLUE)") (class "Default")
      (node (ref "J1") (pin "3") (pinfunction "BLUE_3") (pintype "passive"))
      (node (ref "R10") (pin "2") (pinfunction "2_2") (pintype "passive"))
      (node (ref "R11") (pin "2") (pinfunction "2_2") (pintype "passive"))
      (node (ref "R9") (pin "2") (pinfunction "2_2") (pintype "passive"))
    )
    (net (code "41") (name "Net-(J1-GREEN)") (class "Default")
      (node (ref "J1") (pin "2") (pinfunction "GREEN_2") (pintype "passive"))
      (node (ref "R5") (pin "2") (pinfunction "2_2") (pintype "passive"))
      (node (ref "R6") (pin "2") (pinfunction "2_2") (pintype "passive"))
      (node (ref "R7") (pin "2") (pinfunction "2_2") (pintype "passive"))
    )
    (net (code "42") (name "Net-(J1-HSYNC)") (class "Default")
      (node (ref "J1") (pin "13") (pinfunction "HSYNC_13") (pintype "passive"))
      (node (ref "R29") (pin "1") (pinfunction "1_1") (pintype "passive"))
    )
    (net (code "43") (name "Net-(J1-RED)") (class "Default")
      (node (ref "J1") (pin "1") (pinfunction "RED_1") (pintype "passive"))
      (node (ref "R2") (pin "2") (pinfunction "2_2") (pintype "passive"))
      (node (ref "R3") (pin "2") (pinfunction "2_2") (pintype "passive"))
      (node (ref "R4") (pin "2") (pinfunction "2_2") (pintype "passive"))
    )
    (net (code "44") (name "Net-(J1-VSYNC)") (class "Default")
      (node (ref "J1") (pin "14") (pinfunction "VSYNC_14") (pintype "passive"))
      (node (ref "R30") (pin "1") (pinfunction "1_1") (pintype "passive"))
    )
    (net (code "45") (name "Net-(J2-CLK)") (class "Default")
      (node (ref "J2") (pin "5") (pinfunction "CLK_5") (pintype "passive"))
      (node (ref "R16") (pin "2") (pinfunction "2_2") (pintype "passive"))
      (node (ref "R18") (pin "1") (pinfunction "1_1") (pintype "passive"))
    )
    (net (code "46") (name "Net-(J2-DATA)") (class "Default")
      (node (ref "J2") (pin "1") (pinfunction "DATA_1") (pintype "passive"))
      (node (ref "R20") (pin "1") (pinfunction "1_1") (pintype "passive"))
      (node (ref "R22") (pin "2") (pinfunction "2_2") (pintype "passive"))
    )
    (net (code "47") (name "Net-(JP1-Pad2)") (class "Default")
      (node (ref "JP1") (pin "2") (pinfunction "2_2") (pintype "passive"))
      (node (ref "R9") (pin "1") (pinfunction "1_1") (pintype "passive"))
    )
    (net (code "48") (name "Net-(JP2-Pad2)") (class "Default")
      (node (ref "JP2") (pin "2") (pinfunction "2_2") (pintype "passive"))
      (node (ref "R5") (pin "1") (pinfunction "1_1") (pintype "passive"))
    )
    (net (code "49") (name "Net-(JP3-Pad2)") (class "Default")
      (node (ref "JP3") (pin "2") (pinfunction "2_2") (pintype "passive"))
      (node (ref "R2") (pin "1") (pinfunction "1_1") (pintype "passive"))
    )
    (net (code "50") (name "Net-(JP4-Pad2)") (class "Default")
      (node (ref "JP4") (pin "2") (pinfunction "2_2") (pintype "passive"))
      (node (ref "P9") (pin "1") (pinfunction "1_1") (pintype "passive"))
    )
    (net (code "51") (name "Net-(JP5-Pad2)") (class "Default")
      (node (ref "JP5") (pin "2") (pinfunction "2_2") (pintype "passive"))
      (node (ref "P10") (pin "1") (pinfunction "1_1") (pintype "passive"))
    )
    (net (code "52") (name "Net-(Q1-D)") (class "Default")
      (node (ref "Q1") (pin "3") (pinfunction "D_3") (pintype "passive"))
      (node (ref "SSEG1") (pin "1") (pinfunction "A1_1") (pintype "passive"))
    )
    (net (code "53") (name "Net-(Q2-D)") (class "Default")
      (node (ref "Q2") (pin "3") (pinfunction "D_3") (pintype "passive"))
      (node (ref "SSEG1") (pin "2") (pinfunction "A2_2") (pintype "passive"))
    )
    (net (code "54") (name "Net-(Q3-D)") (class "Default")
      (node (ref "Q3") (pin "3") (pinfunction "D_3") (pintype "passive"))
      (node (ref "SSEG1") (pin "4") (pinfunction "L*_4") (pintype "passive"))
    )
    (net (code "55") (name "Net-(Q4-D)") (class "Default")
      (node (ref "Q4") (pin "3") (pinfunction "D_3") (pintype "passive"))
      (node (ref "SSEG1") (pin "6") (pinfunction "A3_6") (pintype "passive"))
    )
    (net (code "56") (name "Net-(Q5-D)") (class "Default")
      (node (ref "Q5") (pin "3") (pinfunction "D_3") (pintype "passive"))
      (node (ref "SSEG1") (pin "8") (pinfunction "A4_8") (pintype "passive"))
    )
    (net (code "57") (name "Net-(SSEG1-A_(L1))") (class "Default")
      (node (ref "R17") (pin "1") (pinfunction "1_1") (pintype "passive"))
      (node (ref "SSEG1") (pin "14") (pinfunction "A_(L1)_14") (pintype "passive"))
    )
    (net (code "58") (name "Net-(SSEG1-B_(L2))") (class "Default")
      (node (ref "R14") (pin "1") (pinfunction "1_1") (pintype "passive"))
      (node (ref "SSEG1") (pin "16") (pinfunction "B_(L2)_16") (pintype "passive"))
    )
    (net (code "59") (name "Net-(SSEG1-C_(L3))") (class "Default")
      (node (ref "R19") (pin "1") (pinfunction "1_1") (pintype "passive"))
      (node (ref "SSEG1") (pin "13") (pinfunction "C_(L3)_13") (pintype "passive"))
    )
    (net (code "60") (name "Net-(SSEG1-D)") (class "Default")
      (node (ref "R8") (pin "1") (pinfunction "1_1") (pintype "passive"))
      (node (ref "SSEG1") (pin "3") (pinfunction "D_3") (pintype "passive"))
    )
    (net (code "61") (name "Net-(SSEG1-DP)") (class "Default")
      (node (ref "R13") (pin "1") (pinfunction "1_1") (pintype "passive"))
      (node (ref "SSEG1") (pin "7") (pinfunction "DP_7") (pintype "passive"))
    )
    (net (code "62") (name "Net-(SSEG1-E)") (class "Default")
      (node (ref "R12") (pin "1") (pinfunction "1_1") (pintype "passive"))
      (node (ref "SSEG1") (pin "5") (pinfunction "E_5") (pintype "passive"))
    )
    (net (code "63") (name "Net-(SSEG1-F)") (class "Default")
      (node (ref "R21") (pin "1") (pinfunction "1_1") (pintype "passive"))
      (node (ref "SSEG1") (pin "11") (pinfunction "F_11") (pintype "passive"))
    )
    (net (code "64") (name "Net-(SSEG1-G)") (class "Default")
      (node (ref "R15") (pin "1") (pinfunction "1_1") (pintype "passive"))
      (node (ref "SSEG1") (pin "15") (pinfunction "G_15") (pintype "passive"))
    )
    (net (code "65") (name "VDD_PS2") (class "Default")
      (node (ref "C3") (pin "2") (pinfunction "2_2") (pintype "passive"))
      (node (ref "C4") (pin "2") (pinfunction "2_2") (pintype "passive"))
      (node (ref "J2") (pin "4") (pinfunction "VCC_4") (pintype "passive"))
      (node (ref "J3") (pin "4") (pinfunction "VCC_4") (pintype "passive"))
      (node (ref "P5") (pin "2") (pinfunction "2_2") (pintype "passive"))
      (node (ref "R18") (pin "2") (pinfunction "2_2") (pintype "passive"))
      (node (ref "R20") (pin "2") (pinfunction "2_2") (pintype "passive"))
      (node (ref "R24") (pin "2") (pinfunction "2_2") (pintype "passive"))
      (node (ref "R25") (pin "2") (pinfunction "2_2") (pintype "passive"))
    )
    (net (code "66") (name "VEXT") (class "Default")
      (node (ref "P10") (pin "2") (pinfunction "2_2") (pintype "passive"))
      (node (ref "P11") (pin "2") (pinfunction "2_2") (pintype "passive"))
      (node (ref "P12") (pin "2") (pinfunction "2_2") (pintype "passive"))
      (node (ref "P13") (pin "2") (pinfunction "2_2") (pintype "passive"))
      (node (ref "P14") (pin "2") (pinfunction "2_2") (pintype "passive"))
      (node (ref "P15") (pin "2") (pinfunction "2_2") (pintype "passive"))
      (node (ref "P16") (pin "2") (pinfunction "2_2") (pintype "passive"))
      (node (ref "P2") (pin "1") (pinfunction "1_1") (pintype "passive"))
      (node (ref "P5") (pin "1") (pinfunction "1_1") (pintype "passive"))
      (node (ref "P9") (pin "2") (pinfunction "2_2") (pintype "passive"))
    )
    (net (code "67") (name "unconnected-(J1-ID0-Pad11)") (class "Default")
      (node (ref "J1") (pin "11") (pinfunction "ID0_11") (pintype "passive"))
    )
    (net (code "68") (name "unconnected-(J1-ID1{slash}SDA-Pad12)") (class "Default")
      (node (ref "J1") (pin "12") (pinfunction "ID1/SDA_12") (pintype "passive"))
    )
    (net (code "69") (name "unconnected-(J1-ID2-Pad4)") (class "Default")
      (node (ref "J1") (pin "4") (pinfunction "ID2_4") (pintype "passive"))
    )
    (net (code "70") (name "unconnected-(J1-ID3{slash}SCL-Pad15)") (class "Default")
      (node (ref "J1") (pin "15") (pinfunction "ID3/SCL_15") (pintype "passive"))
    )
    (net (code "71") (name "unconnected-(J1-KEY-Pad9)") (class "Default")
      (node (ref "J1") (pin "9") (pinfunction "KEY_9") (pintype "passive"))
    )
    (net (code "72") (name "unconnected-(J2-NC-Pad2)") (class "Default")
      (node (ref "J2") (pin "2") (pinfunction "NC_2") (pintype "passive+no_connect"))
    )
    (net (code "73") (name "unconnected-(J2-NC-Pad6)") (class "Default")
      (node (ref "J2") (pin "6") (pinfunction "NC_6") (pintype "passive+no_connect"))
    )
    (net (code "74") (name "unconnected-(J3-NC-Pad2)") (class "Default")
      (node (ref "J3") (pin "2") (pinfunction "NC_2") (pintype "passive+no_connect"))
    )
    (net (code "75") (name "unconnected-(J3-NC-Pad6)") (class "Default")
      (node (ref "J3") (pin "6") (pinfunction "NC_6") (pintype "passive+no_connect"))
    )
    (net (code "76") (name "unconnected-(J6-Pad4)") (class "Default")
      (node (ref "J6") (pin "4") (pinfunction "4_4") (pintype "passive"))
    )
    (net (code "77") (name "unconnected-(P3-VCC-Pad6)") (class "Default")
      (node (ref "P3") (pin "6") (pinfunction "VCC_6") (pintype "power_in+no_connect"))
    )
    (net (code "78") (name "unconnected-(P3-VCC-Pad12)") (class "Default")
      (node (ref "P3") (pin "12") (pinfunction "VCC_12") (pintype "power_in+no_connect"))
    )
    (net (code "79") (name "unconnected-(P7-VCC-Pad6)") (class "Default")
      (node (ref "P7") (pin "6") (pinfunction "VCC_6") (pintype "power_in+no_connect"))
    )
    (net (code "80") (name "unconnected-(P7-VCC-Pad12)") (class "Default")
      (node (ref "P7") (pin "12") (pinfunction "VCC_12") (pintype "power_in+no_connect"))
    )
    (net (code "81") (name "unconnected-(P8-VCC-Pad6)") (class "Default")
      (node (ref "P8") (pin "6") (pinfunction "VCC_6") (pintype "power_in+no_connect"))
    )
    (net (code "82") (name "unconnected-(P8-VCC-Pad12)") (class "Default")
      (node (ref "P8") (pin "12") (pinfunction "VCC_12") (pintype "power_in+no_connect"))
    )
    (net (code "83") (name "unconnected-(P11-Pad1)") (class "Default")
      (node (ref "P11") (pin "1") (pinfunction "1_1") (pintype "passive"))
    )
    (net (code "84") (name "unconnected-(P12-Pad1)") (class "Default")
      (node (ref "P12") (pin "1") (pinfunction "1_1") (pintype "passive"))
    )
    (net (code "85") (name "unconnected-(P13-Pad1)") (class "Default")
      (node (ref "P13") (pin "1") (pinfunction "1_1") (pintype "passive"))
    )
    (net (code "86") (name "unconnected-(P14-Pad1)") (class "Default")
      (node (ref "P14") (pin "1") (pinfunction "1_1") (pintype "passive"))
    )
    (net (code "87") (name "unconnected-(P15-Pad1)") (class "Default")
      (node (ref "P15") (pin "1") (pinfunction "1_1") (pintype "passive"))
    )
    (net (code "88") (name "unconnected-(P16-Pad1)") (class "Default")
      (node (ref "P16") (pin "1") (pinfunction "1_1") (pintype "passive"))
    )
  )
)
